# Domino_USB_MicroSD.net
KiCad netlist of a schematic drawn in EAGLE
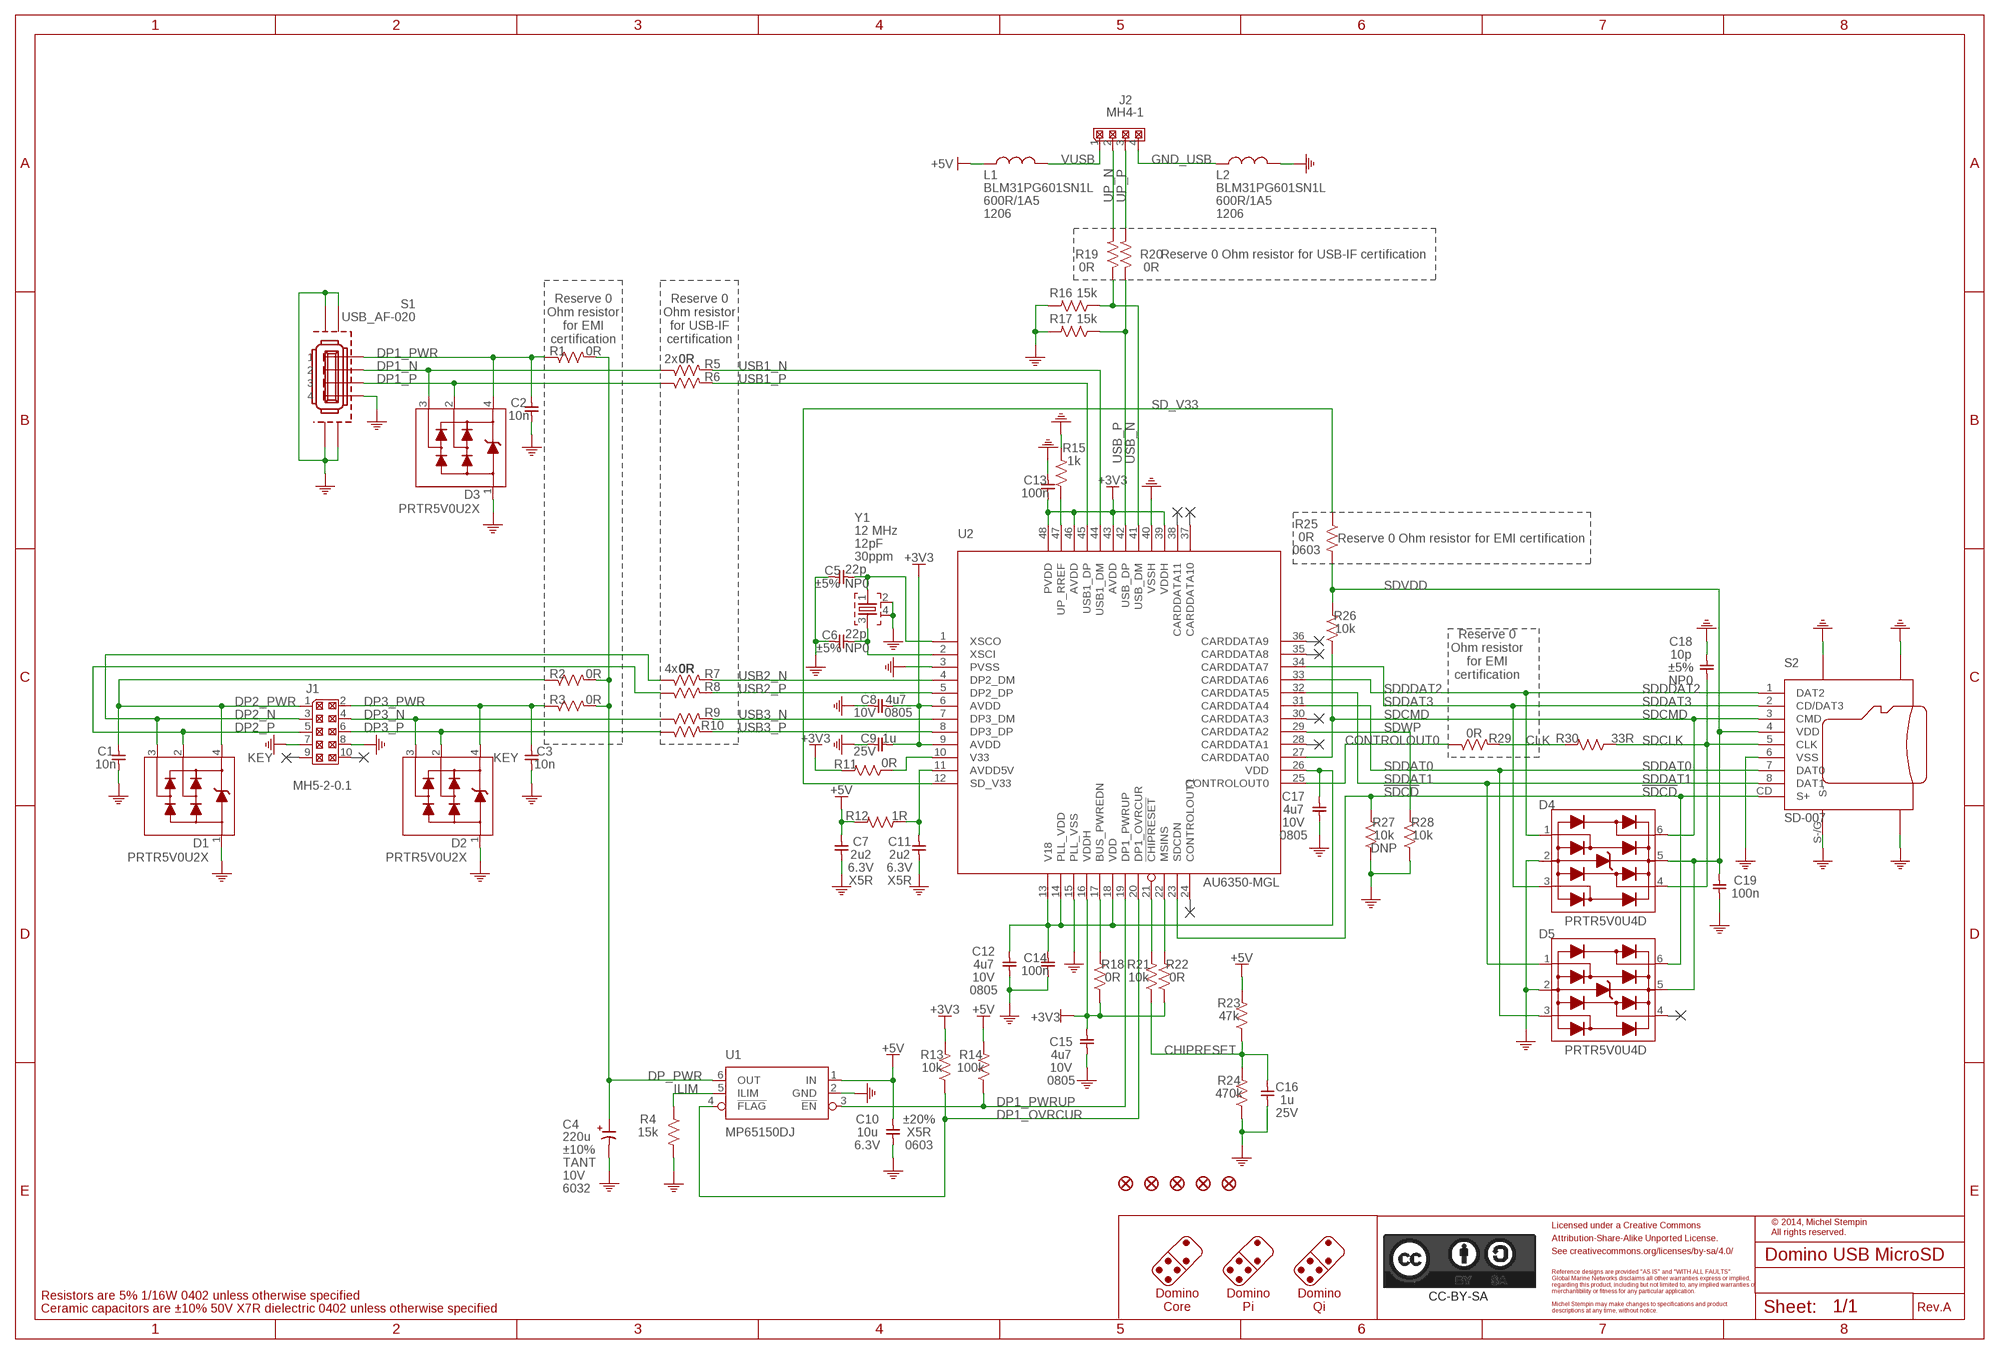
[diagram p0: schematic, sheet 1]

(export (version "E")
  (design (tool "Eeschema 10.0.6"))
  (components
    (comp (ref "C1")
      (value "10n")
      (footprint "eagle-import:C0402")
      (fields (field (name "PARTNO") "C0402_10n_X7R_10%_CER_50V"))
      (libsource (lib "eagle-import") (part "CAP_0402"))
    )
    (comp (ref "C2")
      (value "10n")
      (footprint "eagle-import:C0402")
      (fields (field (name "PARTNO") "C0402_10n_X7R_10%_CER_50V"))
      (libsource (lib "eagle-import") (part "CAP_0402"))
    )
    (comp (ref "C3")
      (value "10n")
      (footprint "eagle-import:C0402")
      (fields (field (name "PARTNO") "C0402_10n_X7R_10%_CER_50V"))
      (libsource (lib "eagle-import") (part "CAP_0402"))
    )
    (comp (ref "C4")
      (value "220u")
      (footprint "eagle-import:C_6032-25")
      (fields
        (field (name "SIZE") "6032")
        (field (name "TYPE") "TANT")
        (field (name "PARTNO") "CPOLC-6032_220u_20%_TANT_10V")
        (field (name "TOL") "±10%")
        (field (name "VOLT") "10V")
      )
      (libsource (lib "eagle-import") (part "CPOL_?C/6032-25"))
    )
    (comp (ref "C5")
      (value "22p")
      (footprint "eagle-import:C0402")
      (fields
        (field (name "PARTNO") "C0402_22p_NP0_5%_CER_50V")
        (field (name "TC") "NP0")
        (field (name "TOL") "±5%")
      )
      (libsource (lib "eagle-import") (part "CAP_0402"))
    )
    (comp (ref "C6")
      (value "22p")
      (footprint "eagle-import:C0402")
      (fields
        (field (name "PARTNO") "C0402_22p_NP0_5%_CER_50V")
        (field (name "TC") "NP0")
        (field (name "TOL") "±5%")
      )
      (libsource (lib "eagle-import") (part "CAP_0402"))
    )
    (comp (ref "C7")
      (value "2u2")
      (footprint "eagle-import:C0402")
      (fields
        (field (name "PARTNO") "C0402_2u2_X5R_10%_CER_6V3")
        (field (name "TC") "X5R")
        (field (name "VOLT") "6.3V")
      )
      (libsource (lib "eagle-import") (part "CAP_0402"))
    )
    (comp (ref "C8")
      (value "4u7")
      (footprint "eagle-import:C0805")
      (fields
        (field (name "SIZE") "0805")
        (field (name "PARTNO") "C0805_4u7_X7R_10%_CER_6V3")
        (field (name "VOLT") "10V")
      )
      (libsource (lib "eagle-import") (part "CAP_0805"))
    )
    (comp (ref "C9")
      (value "1u")
      (footprint "eagle-import:C0402")
      (fields (field (name "PARTNO") "C0402_1u_X7R_10%_CER_25V") (field (name "VOLT") "25V"))
      (libsource (lib "eagle-import") (part "CAP_0402"))
    )
    (comp (ref "C10")
      (value "10u")
      (footprint "eagle-import:C0603")
      (fields
        (field (name "SIZE") "0603")
        (field (name "PARTNO") "C0603_10u_X5R_20%_CER_6V3")
        (field (name "TC") "X5R")
        (field (name "TOL") "±20%")
        (field (name "VOLT") "6.3V")
      )
      (libsource (lib "eagle-import") (part "CAP_0603"))
    )
    (comp (ref "C11")
      (value "2u2")
      (footprint "eagle-import:C0402")
      (fields
        (field (name "PARTNO") "C0402_2u2_X5R_10%_CER_6V3")
        (field (name "TC") "X5R")
        (field (name "VOLT") "6.3V")
      )
      (libsource (lib "eagle-import") (part "CAP_0402"))
    )
    (comp (ref "C12")
      (value "4u7")
      (footprint "eagle-import:C0805")
      (fields
        (field (name "SIZE") "0805")
        (field (name "PARTNO") "C0805_4u7_X7R_10%_CER_6V3")
        (field (name "VOLT") "10V")
      )
      (libsource (lib "eagle-import") (part "CAP_0805"))
    )
    (comp (ref "C13")
      (value "100n")
      (footprint "eagle-import:C0402")
      (fields (field (name "PARTNO") "C0402_100n_X7R_10%_CER_50V"))
      (libsource (lib "eagle-import") (part "CAP_0402"))
    )
    (comp (ref "C14")
      (value "100n")
      (footprint "eagle-import:C0402")
      (fields (field (name "PARTNO") "C0402_100n_X7R_10%_CER_50V"))
      (libsource (lib "eagle-import") (part "CAP_0402"))
    )
    (comp (ref "C15")
      (value "4u7")
      (footprint "eagle-import:C0805")
      (fields
        (field (name "SIZE") "0805")
        (field (name "PARTNO") "C0805_4u7_X7R_10%_CER_6V3")
        (field (name "VOLT") "10V")
      )
      (libsource (lib "eagle-import") (part "CAP_0805"))
    )
    (comp (ref "C16")
      (value "1u")
      (footprint "eagle-import:C0402")
      (fields (field (name "PARTNO") "C0402_1u_X7R_10%_CER_25V") (field (name "VOLT") "25V"))
      (libsource (lib "eagle-import") (part "CAP_0402"))
    )
    (comp (ref "C17")
      (value "4u7")
      (footprint "eagle-import:C0805")
      (fields
        (field (name "SIZE") "0805")
        (field (name "PARTNO") "C0805_4u7_X7R_10%_CER_6V3")
        (field (name "VOLT") "10V")
      )
      (libsource (lib "eagle-import") (part "CAP_0805"))
    )
    (comp (ref "C18")
      (value "10p")
      (footprint "eagle-import:C0402")
      (fields
        (field (name "PARTNO") "C0402_10p_NP0_5%_CER_50V")
        (field (name "TC") "NP0")
        (field (name "TOL") "±5%")
      )
      (libsource (lib "eagle-import") (part "CAP_0402"))
    )
    (comp (ref "C19")
      (value "100n")
      (footprint "eagle-import:C0402")
      (fields (field (name "PARTNO") "C0402_100n_X7R_10%_CER_50V"))
      (libsource (lib "eagle-import") (part "CAP_0402"))
    )
    (comp (ref "CC-BY-SA1")
      (value "CC-BY-SA_LOGO")
      (footprint "eagle-import:CC-BY-SA_LOGO")
      (libsource (lib "eagle-import") (part "CC-BY-SA_LOGO"))
    )
    (comp (ref "D1")
      (value "PRTR5V0U2X")
      (footprint "eagle-import:SOT143B")
      (libsource (lib "eagle-import") (part "PRTR5V0U2X"))
    )
    (comp (ref "D2")
      (value "PRTR5V0U2X")
      (footprint "eagle-import:SOT143B")
      (libsource (lib "eagle-import") (part "PRTR5V0U2X"))
    )
    (comp (ref "D3")
      (value "PRTR5V0U2X")
      (footprint "eagle-import:SOT143B")
      (libsource (lib "eagle-import") (part "PRTR5V0U2X"))
    )
    (comp (ref "D4")
      (value "PRTR5V0U4D")
      (footprint "eagle-import:SOT23-6")
      (libsource (lib "eagle-import") (part "PRTR5V0U4D"))
    )
    (comp (ref "D5")
      (value "PRTR5V0U4D")
      (footprint "eagle-import:SOT23-6")
      (libsource (lib "eagle-import") (part "PRTR5V0U4D"))
    )
    (comp (ref "F1")
      (value "FIDUCIAL")
      (footprint "eagle-import:FIDUCIAL")
      (libsource (lib "eagle-import") (part "FIDUCIAL"))
    )
    (comp (ref "F2")
      (value "FIDUCIAL")
      (footprint "eagle-import:FIDUCIAL")
      (libsource (lib "eagle-import") (part "FIDUCIAL"))
    )
    (comp (ref "F4")
      (value "FIDUCIAL")
      (footprint "eagle-import:FIDUCIAL")
      (libsource (lib "eagle-import") (part "FIDUCIAL"))
    )
    (comp (ref "F5")
      (value "FIDUCIAL")
      (footprint "eagle-import:FIDUCIAL")
      (libsource (lib "eagle-import") (part "FIDUCIAL"))
    )
    (comp (ref "F6")
      (value "FIDUCIAL")
      (footprint "eagle-import:FIDUCIAL")
      (libsource (lib "eagle-import") (part "FIDUCIAL"))
    )
    (comp (ref "J1")
      (value "MH5-2-0.1")
      (footprint "eagle-import:MH05-2-0.1")
      (libsource (lib "eagle-import") (part "MH5-2"))
    )
    (comp (ref "J2")
      (value "MH4-1")
      (footprint "eagle-import:MH4-1-0.1")
      (fields (field (name "PARTNO") "MH4-1-0.1"))
      (libsource (lib "eagle-import") (part "MH4-1"))
    )
    (comp (ref "L1")
      (value "BLM31PG601SN1L")
      (footprint "eagle-import:FB1206")
      (fields (field (name "SIZE") "1206") (field (name "OPT") "600R/1A5"))
      (libsource (lib "eagle-import") (part "FB_1206"))
    )
    (comp (ref "L2")
      (value "BLM31PG601SN1L")
      (footprint "eagle-import:FB1206")
      (fields (field (name "SIZE") "1206") (field (name "OPT") "600R/1A5"))
      (libsource (lib "eagle-import") (part "FB_1206"))
    )
    (comp (ref "R1")
      (value "0R")
      (footprint "eagle-import:R0402")
      (fields (field (name "PARTNO") "R0402_0R_5%_62.5mW"))
      (libsource (lib "eagle-import") (part "RES_0402"))
    )
    (comp (ref "R2")
      (value "0R")
      (footprint "eagle-import:R0402")
      (fields (field (name "PARTNO") "R0402_0R_5%_62.5mW"))
      (libsource (lib "eagle-import") (part "RES_0402"))
    )
    (comp (ref "R3")
      (value "0R")
      (footprint "eagle-import:R0402")
      (fields (field (name "PARTNO") "R0402_0R_5%_62.5mW"))
      (libsource (lib "eagle-import") (part "RES_0402"))
    )
    (comp (ref "R4")
      (value "15k")
      (footprint "eagle-import:R0402")
      (fields (field (name "PARTNO") "R0402_15k_5%_62.5mW"))
      (libsource (lib "eagle-import") (part "RES_0402"))
    )
    (comp (ref "R5")
      (value "0R")
      (footprint "eagle-import:R0402")
      (fields (field (name "PARTNO") "R0402_0R_5%_62.5mW"))
      (libsource (lib "eagle-import") (part "RES_0402"))
    )
    (comp (ref "R6")
      (value "0R")
      (footprint "eagle-import:R0402")
      (fields (field (name "PARTNO") "R0402_0R_5%_62.5mW"))
      (libsource (lib "eagle-import") (part "RES_0402"))
    )
    (comp (ref "R7")
      (value "0R")
      (footprint "eagle-import:R0402")
      (fields (field (name "PARTNO") "R0402_0R_5%_62.5mW"))
      (libsource (lib "eagle-import") (part "RES_0402"))
    )
    (comp (ref "R8")
      (value "0R")
      (footprint "eagle-import:R0402")
      (fields (field (name "PARTNO") "R0402_0R_5%_62.5mW"))
      (libsource (lib "eagle-import") (part "RES_0402"))
    )
    (comp (ref "R9")
      (value "0R")
      (footprint "eagle-import:R0402")
      (fields (field (name "PARTNO") "R0402_0R_5%_62.5mW"))
      (libsource (lib "eagle-import") (part "RES_0402"))
    )
    (comp (ref "R10")
      (value "0R")
      (footprint "eagle-import:R0402")
      (fields (field (name "PARTNO") "R0402_0R_5%_62.5mW"))
      (libsource (lib "eagle-import") (part "RES_0402"))
    )
    (comp (ref "R11")
      (value "0R")
      (footprint "eagle-import:R0402")
      (fields (field (name "PARTNO") "R0402_0R_5%_62.5mW"))
      (libsource (lib "eagle-import") (part "RES_0402"))
    )
    (comp (ref "R12")
      (value "1R")
      (footprint "eagle-import:R0402")
      (fields (field (name "PARTNO") "R0402_1R_5%_62.5mW"))
      (libsource (lib "eagle-import") (part "RES_0402"))
    )
    (comp (ref "R13")
      (value "10k")
      (footprint "eagle-import:R0402")
      (fields (field (name "PARTNO") "R0402_10k_5%_62.5mW"))
      (libsource (lib "eagle-import") (part "RES_0402"))
    )
    (comp (ref "R14")
      (value "100k")
      (footprint "eagle-import:R0402")
      (fields (field (name "PARTNO") "R0402_100k_5%_62.5mW"))
      (libsource (lib "eagle-import") (part "RES_0402"))
    )
    (comp (ref "R15")
      (value "1k")
      (footprint "eagle-import:R0402")
      (fields (field (name "PARTNO") "R0402_1k_5%_62.5mW"))
      (libsource (lib "eagle-import") (part "RES_0402"))
    )
    (comp (ref "R16")
      (value "15k")
      (footprint "eagle-import:R0402")
      (fields (field (name "PARTNO") "R0402_15k_5%_62.5mW"))
      (libsource (lib "eagle-import") (part "RES_0402"))
    )
    (comp (ref "R17")
      (value "15k")
      (footprint "eagle-import:R0402")
      (fields (field (name "PARTNO") "R0402_15k_5%_62.5mW"))
      (libsource (lib "eagle-import") (part "RES_0402"))
    )
    (comp (ref "R18")
      (value "0R")
      (footprint "eagle-import:R0402")
      (fields (field (name "PARTNO") "R0402_0R_5%_62.5mW"))
      (libsource (lib "eagle-import") (part "RES_0402"))
    )
    (comp (ref "R19")
      (value "0R")
      (footprint "eagle-import:R0402")
      (fields (field (name "PARTNO") "R0402_0R_5%_62.5mW"))
      (libsource (lib "eagle-import") (part "RES_0402"))
    )
    (comp (ref "R20")
      (value "0R")
      (footprint "eagle-import:R0402")
      (fields (field (name "PARTNO") "R0402_0R_5%_62.5mW"))
      (libsource (lib "eagle-import") (part "RES_0402"))
    )
    (comp (ref "R21")
      (value "10k")
      (footprint "eagle-import:R0402")
      (fields (field (name "PARTNO") "R0402_10k_5%_62.5mW"))
      (libsource (lib "eagle-import") (part "RES_0402"))
    )
    (comp (ref "R22")
      (value "0R")
      (footprint "eagle-import:R0402")
      (fields (field (name "PARTNO") "R0402_0R_5%_62.5mW"))
      (libsource (lib "eagle-import") (part "RES_0402"))
    )
    (comp (ref "R23")
      (value "47k")
      (footprint "eagle-import:R0402")
      (fields (field (name "PARTNO") "R0402_47k_5%_62.5mW"))
      (libsource (lib "eagle-import") (part "RES_0402"))
    )
    (comp (ref "R24")
      (value "470k")
      (footprint "eagle-import:R0402")
      (fields (field (name "PARTNO") "R0402_470k_5%_62.5mW"))
      (libsource (lib "eagle-import") (part "RES_0402"))
    )
    (comp (ref "R25")
      (value "0R")
      (footprint "eagle-import:R0603")
      (fields (field (name "SIZE") "0603") (field (name "PARTNO") "R0603_0R_5%_125mW"))
      (libsource (lib "eagle-import") (part "RES_0603"))
    )
    (comp (ref "R26")
      (value "10k")
      (footprint "eagle-import:R0402")
      (fields (field (name "PARTNO") "R0402_10k_5%_62.5mW"))
      (libsource (lib "eagle-import") (part "RES_0402"))
    )
    (comp (ref "R27")
      (value "10k")
      (footprint "eagle-import:R0402")
      (fields (field (name "PARTNO") "R0402_10k_5%_62.5mW"))
      (libsource (lib "eagle-import") (part "RES_0402"))
    )
    (comp (ref "R28")
      (value "10k")
      (footprint "eagle-import:R0402")
      (fields (field (name "PARTNO") "R0402_10k_5%_62.5mW"))
      (libsource (lib "eagle-import") (part "RES_0402"))
    )
    (comp (ref "R29")
      (value "0R")
      (footprint "eagle-import:R0402")
      (fields (field (name "PARTNO") "R0402_0R_5%_62.5mW"))
      (libsource (lib "eagle-import") (part "RES_0402"))
    )
    (comp (ref "R30")
      (value "33R")
      (footprint "eagle-import:R0402")
      (fields (field (name "PARTNO") "R0402_33R_5%_62.5mW"))
      (libsource (lib "eagle-import") (part "RES_0402"))
    )
    (comp (ref "S1")
      (value "USB_AF-020")
      (footprint "eagle-import:USB_AF-020")
      (libsource (lib "eagle-import") (part "USB_AF-020"))
    )
    (comp (ref "S2")
      (value "SD-007")
      (footprint "eagle-import:SD-007")
      (libsource (lib "eagle-import") (part "MICRO-SD"))
    )
    (comp (ref "U1")
      (value "MP65150DJ")
      (footprint "eagle-import:SOT23-6")
      (libsource (lib "eagle-import") (part "MP65150DJ"))
    )
    (comp (ref "U2")
      (value "AU6350-MGL")
      (footprint "eagle-import:LQFP-48_7X7")
      (libsource (lib "eagle-import") (part "AU6350-MGL"))
    )
    (comp (ref "Y1")
      (value "12 MHz")
      (footprint "eagle-import:CRYSTAL_32X25")
      (fields
        (field (name "LOAD") "12pF")
        (field (name "PARTNO") "CRYSTAL_32X25_2SH_12PF_30PPM")
        (field (name "TOL") "30ppm")
      )
      (libsource (lib "eagle-import") (part "CRYSTAL_2SH"))
    )
  )
  (nets
    (net (code "1") (name "+3V3") (class "Default")
      (node (ref "C13") (pin "2") (pinfunction "2_2") (pintype "passive"))
      (node (ref "C15") (pin "2") (pinfunction "2_2") (pintype "passive"))
      (node (ref "C8") (pin "2") (pinfunction "2_2") (pintype "passive"))
      (node (ref "C9") (pin "2") (pinfunction "2_2") (pintype "passive"))
      (node (ref "R11") (pin "2") (pinfunction "2_2") (pintype "passive"))
      (node (ref "R13") (pin "2") (pinfunction "2_2") (pintype "passive"))
      (node (ref "R18") (pin "1") (pinfunction "1_1") (pintype "passive"))
      (node (ref "R22") (pin "1") (pinfunction "1_1") (pintype "passive"))
      (node (ref "U2") (pin "16") (pinfunction "VDDH_16") (pintype "power_in"))
      (node (ref "U2") (pin "39") (pinfunction "VDDH_39") (pintype "power_in"))
      (node (ref "U2") (pin "43") (pinfunction "AVDD_43") (pintype "power_in"))
      (node (ref "U2") (pin "46") (pinfunction "AVDD_46") (pintype "power_in"))
      (node (ref "U2") (pin "48") (pinfunction "PVDD_48") (pintype "power_in"))
      (node (ref "U2") (pin "6") (pinfunction "AVDD_6") (pintype "power_in"))
      (node (ref "U2") (pin "9") (pinfunction "AVDD_9") (pintype "power_in"))
    )
    (net (code "2") (name "+5V") (class "Default")
      (node (ref "C10") (pin "1") (pinfunction "1_1") (pintype "passive"))
      (node (ref "C7") (pin "1") (pinfunction "1_1") (pintype "passive"))
      (node (ref "L1") (pin "2") (pinfunction "2_2") (pintype "passive"))
      (node (ref "R12") (pin "2") (pinfunction "2_2") (pintype "passive"))
      (node (ref "R14") (pin "2") (pinfunction "2_2") (pintype "passive"))
      (node (ref "R23") (pin "2") (pinfunction "2_2") (pintype "passive"))
      (node (ref "U1") (pin "1") (pinfunction "IN_1") (pintype "power_in"))
    )
    (net (code "3") (name "/CHIPRESET") (class "Default")
      (node (ref "C16") (pin "1") (pinfunction "1_1") (pintype "passive"))
      (node (ref "R21") (pin "1") (pinfunction "1_1") (pintype "passive"))
      (node (ref "R23") (pin "1") (pinfunction "1_1") (pintype "passive"))
      (node (ref "R24") (pin "2") (pinfunction "2_2") (pintype "passive"))
    )
    (net (code "4") (name "/CLK") (class "Default")
      (node (ref "R29") (pin "2") (pinfunction "2_2") (pintype "passive"))
      (node (ref "R30") (pin "2") (pinfunction "2_2") (pintype "passive"))
    )
    (net (code "5") (name "/CONTROLOUT0") (class "Default")
      (node (ref "R29") (pin "1") (pinfunction "1_1") (pintype "passive"))
      (node (ref "U2") (pin "25") (pinfunction "CONTROLOUT0_25") (pintype "output"))
    )
    (net (code "6") (name "/DP1_N") (class "Default")
      (node (ref "D3") (pin "3") (pinfunction "P$3_3") (pintype "passive"))
      (node (ref "R5") (pin "1") (pinfunction "1_1") (pintype "passive"))
      (node (ref "S1") (pin "2") (pinfunction "2_2") (pintype "passive"))
    )
    (net (code "7") (name "/DP1_OVRCUR") (class "Default")
      (node (ref "R13") (pin "1") (pinfunction "1_1") (pintype "passive"))
      (node (ref "U1") (pin "4") (pinfunction "~{FLAG}_4") (pintype "open_collector"))
      (node (ref "U2") (pin "20") (pinfunction "DP1_OVRCUR_20") (pintype "input"))
    )
    (net (code "8") (name "/DP1_P") (class "Default")
      (node (ref "D3") (pin "2") (pinfunction "P$2_2") (pintype "passive"))
      (node (ref "R6") (pin "1") (pinfunction "1_1") (pintype "passive"))
      (node (ref "S1") (pin "3") (pinfunction "3_3") (pintype "passive"))
    )
    (net (code "9") (name "/DP1_PWR") (class "Default")
      (node (ref "C2") (pin "1") (pinfunction "1_1") (pintype "passive"))
      (node (ref "D3") (pin "4") (pinfunction "P$4_4") (pintype "passive"))
      (node (ref "R1") (pin "1") (pinfunction "1_1") (pintype "passive"))
      (node (ref "S1") (pin "1") (pinfunction "1_1") (pintype "passive"))
    )
    (net (code "10") (name "/DP1_PWRUP") (class "Default")
      (node (ref "R14") (pin "1") (pinfunction "1_1") (pintype "passive"))
      (node (ref "U1") (pin "3") (pinfunction "~{EN}_3") (pintype "input"))
      (node (ref "U2") (pin "19") (pinfunction "DP1_PWRUP_19") (pintype "output"))
    )
    (net (code "11") (name "/DP2_N") (class "Default")
      (node (ref "D1") (pin "3") (pinfunction "P$3_3") (pintype "passive"))
      (node (ref "J1") (pin "3") (pinfunction "3_3") (pintype "passive"))
      (node (ref "R7") (pin "1") (pinfunction "1_1") (pintype "passive"))
    )
    (net (code "12") (name "/DP2_P") (class "Default")
      (node (ref "D1") (pin "2") (pinfunction "P$2_2") (pintype "passive"))
      (node (ref "J1") (pin "5") (pinfunction "5_5") (pintype "passive"))
      (node (ref "R8") (pin "1") (pinfunction "1_1") (pintype "passive"))
    )
    (net (code "13") (name "/DP2_PWR") (class "Default")
      (node (ref "C1") (pin "1") (pinfunction "1_1") (pintype "passive"))
      (node (ref "D1") (pin "4") (pinfunction "P$4_4") (pintype "passive"))
      (node (ref "J1") (pin "1") (pinfunction "1_1") (pintype "passive"))
      (node (ref "R2") (pin "1") (pinfunction "1_1") (pintype "passive"))
    )
    (net (code "14") (name "/DP3_N") (class "Default")
      (node (ref "D2") (pin "3") (pinfunction "P$3_3") (pintype "passive"))
      (node (ref "J1") (pin "4") (pinfunction "4_4") (pintype "passive"))
      (node (ref "R9") (pin "1") (pinfunction "1_1") (pintype "passive"))
    )
    (net (code "15") (name "/DP3_P") (class "Default")
      (node (ref "D2") (pin "2") (pinfunction "P$2_2") (pintype "passive"))
      (node (ref "J1") (pin "6") (pinfunction "6_6") (pintype "passive"))
      (node (ref "R10") (pin "1") (pinfunction "1_1") (pintype "passive"))
    )
    (net (code "16") (name "/DP3_PWR") (class "Default")
      (node (ref "C3") (pin "1") (pinfunction "1_1") (pintype "passive"))
      (node (ref "D2") (pin "4") (pinfunction "P$4_4") (pintype "passive"))
      (node (ref "J1") (pin "2") (pinfunction "2_2") (pintype "passive"))
      (node (ref "R3") (pin "1") (pinfunction "1_1") (pintype "passive"))
    )
    (net (code "17") (name "/DP_PWR") (class "Default")
      (node (ref "C4") (pin "1") (pinfunction "+_1") (pintype "passive"))
      (node (ref "R1") (pin "2") (pinfunction "2_2") (pintype "passive"))
      (node (ref "R2") (pin "2") (pinfunction "2_2") (pintype "passive"))
      (node (ref "R3") (pin "2") (pinfunction "2_2") (pintype "passive"))
      (node (ref "U1") (pin "6") (pinfunction "OUT_6") (pintype "power_in"))
    )
    (net (code "18") (name "/GND_USB") (class "Default")
      (node (ref "J2") (pin "4") (pinfunction "4_4") (pintype "passive"))
      (node (ref "L2") (pin "2") (pinfunction "2_2") (pintype "passive"))
    )
    (net (code "19") (name "/ILIM") (class "Default")
      (node (ref "R4") (pin "1") (pinfunction "1_1") (pintype "passive"))
      (node (ref "U1") (pin "5") (pinfunction "ILIM_5") (pintype "passive"))
    )
    (net (code "20") (name "/SDCLK") (class "Default")
      (node (ref "C18") (pin "1") (pinfunction "1_1") (pintype "passive"))
      (node (ref "D4") (pin "4") (pinfunction "I/O3_4") (pintype "passive"))
      (node (ref "R30") (pin "1") (pinfunction "1_1") (pintype "passive"))
      (node (ref "S2") (pin "5") (pinfunction "CLK_5") (pintype "input"))
    )
    (net (code "21") (name "/SDCMD") (class "Default")
      (node (ref "D4") (pin "6") (pinfunction "I/O4_6") (pintype "passive"))
      (node (ref "R26") (pin "1") (pinfunction "1_1") (pintype "passive"))
      (node (ref "S2") (pin "3") (pinfunction "CMD_3") (pintype "input"))
      (node (ref "U2") (pin "27") (pinfunction "CARDDATA0_27") (pintype "bidirectional"))
    )
    (net (code "22") (name "/SDDAT0") (class "Default")
      (node (ref "D5") (pin "3") (pinfunction "I/O2_3") (pintype "passive"))
      (node (ref "S2") (pin "7") (pinfunction "DAT0_7") (pintype "bidirectional"))
      (node (ref "U2") (pin "31") (pinfunction "CARDDATA4_31") (pintype "bidirectional"))
    )
    (net (code "23") (name "/SDDAT1") (class "Default")
      (node (ref "D5") (pin "1") (pinfunction "I/O1_1") (pintype "passive"))
      (node (ref "S2") (pin "8") (pinfunction "DAT1_8") (pintype "bidirectional"))
      (node (ref "U2") (pin "32") (pinfunction "CARDDATA5_32") (pintype "bidirectional"))
    )
    (net (code "24") (name "/SDDAT3") (class "Default")
      (node (ref "D4") (pin "3") (pinfunction "I/O2_3") (pintype "passive"))
      (node (ref "S2") (pin "2") (pinfunction "CD/DAT3_2") (pintype "bidirectional"))
      (node (ref "U2") (pin "34") (pinfunction "CARDDATA7_34") (pintype "bidirectional"))
    )
    (net (code "25") (name "/SDDDAT2") (class "Default")
      (node (ref "D4") (pin "1") (pinfunction "I/O1_1") (pintype "passive"))
      (node (ref "S2") (pin "1") (pinfunction "DAT2_1") (pintype "bidirectional"))
      (node (ref "U2") (pin "33") (pinfunction "CARDDATA6_33") (pintype "bidirectional"))
    )
    (net (code "26") (name "/SDVDD") (class "Default")
      (node (ref "C19") (pin "1") (pinfunction "1_1") (pintype "passive"))
      (node (ref "D4") (pin "5") (pinfunction "VCC_5") (pintype "passive"))
      (node (ref "D5") (pin "5") (pinfunction "VCC_5") (pintype "passive"))
      (node (ref "R25") (pin "2") (pinfunction "2_2") (pintype "passive"))
      (node (ref "R26") (pin "2") (pinfunction "2_2") (pintype "passive"))
      (node (ref "S2") (pin "4") (pinfunction "VDD_4") (pintype "power_in"))
    )
    (net (code "27") (name "/SDWP") (class "Default")
      (node (ref "R28") (pin "2") (pinfunction "2_2") (pintype "passive"))
      (node (ref "U2") (pin "29") (pinfunction "CARDDATA2_29") (pintype "bidirectional"))
    )
    (net (code "28") (name "/SD_V33") (class "Default")
      (node (ref "R25") (pin "1") (pinfunction "1_1") (pintype "passive"))
      (node (ref "U2") (pin "12") (pinfunction "SD_V33_12") (pintype "power_in"))
    )
    (net (code "29") (name "/UP_N") (class "Default")
      (node (ref "J2") (pin "2") (pinfunction "2_2") (pintype "passive"))
      (node (ref "R19") (pin "2") (pinfunction "2_2") (pintype "passive"))
    )
    (net (code "30") (name "/UP_P") (class "Default")
      (node (ref "J2") (pin "3") (pinfunction "3_3") (pintype "passive"))
      (node (ref "R20") (pin "2") (pinfunction "2_2") (pintype "passive"))
    )
    (net (code "31") (name "/USB1_N") (class "Default")
      (node (ref "R5") (pin "2") (pinfunction "2_2") (pintype "passive"))
      (node (ref "U2") (pin "44") (pinfunction "USB1_DM_44") (pintype "passive"))
    )
    (net (code "32") (name "/USB1_P") (class "Default")
      (node (ref "R6") (pin "2") (pinfunction "2_2") (pintype "passive"))
      (node (ref "U2") (pin "45") (pinfunction "USB1_DP_45") (pintype "passive"))
    )
    (net (code "33") (name "/USB2_N") (class "Default")
      (node (ref "R7") (pin "2") (pinfunction "2_2") (pintype "passive"))
      (node (ref "U2") (pin "4") (pinfunction "DP2_DM_4") (pintype "passive"))
    )
    (net (code "34") (name "/USB2_P") (class "Default")
      (node (ref "R8") (pin "2") (pinfunction "2_2") (pintype "passive"))
      (node (ref "U2") (pin "5") (pinfunction "DP2_DP_5") (pintype "passive"))
    )
    (net (code "35") (name "/USB3_N") (class "Default")
      (node (ref "R9") (pin "2") (pinfunction "2_2") (pintype "passive"))
      (node (ref "U2") (pin "7") (pinfunction "DP3_DM_7") (pintype "passive"))
    )
    (net (code "36") (name "/USB3_P") (class "Default")
      (node (ref "R10") (pin "2") (pinfunction "2_2") (pintype "passive"))
      (node (ref "U2") (pin "8") (pinfunction "DP3_DP_8") (pintype "passive"))
    )
    (net (code "37") (name "/USB_N") (class "Default")
      (node (ref "R16") (pin "1") (pinfunction "1_1") (pintype "passive"))
      (node (ref "R19") (pin "1") (pinfunction "1_1") (pintype "passive"))
      (node (ref "U2") (pin "41") (pinfunction "USB_DM_41") (pintype "passive"))
    )
    (net (code "38") (name "/USB_P") (class "Default")
      (node (ref "R17") (pin "1") (pinfunction "1_1") (pintype "passive"))
      (node (ref "R20") (pin "1") (pinfunction "1_1") (pintype "passive"))
      (node (ref "U2") (pin "42") (pinfunction "USB_DP_42") (pintype "passive"))
    )
    (net (code "39") (name "/VUSB") (class "Default")
      (node (ref "J2") (pin "1") (pinfunction "1_1") (pintype "passive"))
      (node (ref "L1") (pin "1") (pinfunction "1_1") (pintype "passive"))
    )
    (net (code "40") (name "/~{SDCD}") (class "Default")
      (node (ref "D5") (pin "6") (pinfunction "I/O4_6") (pintype "passive"))
      (node (ref "R27") (pin "2") (pinfunction "2_2") (pintype "passive"))
      (node (ref "S2") (pin "CD") (pinfunction "S+_CD") (pintype "output"))
      (node (ref "U2") (pin "23") (pinfunction "SDCDN_23") (pintype "input"))
    )
    (net (code "41") (name "GND") (class "Default")
      (node (ref "C1") (pin "2") (pinfunction "2_2") (pintype "passive"))
      (node (ref "C10") (pin "2") (pinfunction "2_2") (pintype "passive"))
      (node (ref "C11") (pin "2") (pinfunction "2_2") (pintype "passive"))
      (node (ref "C12") (pin "1") (pinfunction "1_1") (pintype "passive"))
      (node (ref "C13") (pin "1") (pinfunction "1_1") (pintype "passive"))
      (node (ref "C14") (pin "2") (pinfunction "2_2") (pintype "passive"))
      (node (ref "C15") (pin "1") (pinfunction "1_1") (pintype "passive"))
      (node (ref "C16") (pin "2") (pinfunction "2_2") (pintype "passive"))
      (node (ref "C17") (pin "1") (pinfunction "1_1") (pintype "passive"))
      (node (ref "C18") (pin "2") (pinfunction "2_2") (pintype "passive"))
      (node (ref "C19") (pin "2") (pinfunction "2_2") (pintype "passive"))
      (node (ref "C2") (pin "2") (pinfunction "2_2") (pintype "passive"))
      (node (ref "C3") (pin "2") (pinfunction "2_2") (pintype "passive"))
      (node (ref "C4") (pin "2") (pinfunction "-_2") (pintype "passive"))
      (node (ref "C5") (pin "1") (pinfunction "1_1") (pintype "passive"))
      (node (ref "C6") (pin "1") (pinfunction "1_1") (pintype "passive"))
      (node (ref "C7") (pin "2") (pinfunction "2_2") (pintype "passive"))
      (node (ref "C8") (pin "1") (pinfunction "1_1") (pintype "passive"))
      (node (ref "C9") (pin "1") (pinfunction "1_1") (pintype "passive"))
      (node (ref "D1") (pin "1") (pinfunction "P$1_1") (pintype "passive"))
      (node (ref "D2") (pin "1") (pinfunction "P$1_1") (pintype "passive"))
      (node (ref "D3") (pin "1") (pinfunction "P$1_1") (pintype "passive"))
      (node (ref "D4") (pin "2") (pinfunction "GND_2") (pintype "passive"))
      (node (ref "D5") (pin "2") (pinfunction "GND_2") (pintype "passive"))
      (node (ref "J1") (pin "7") (pinfunction "7_7") (pintype "passive"))
      (node (ref "J1") (pin "8") (pinfunction "8_8") (pintype "passive"))
      (node (ref "L2") (pin "1") (pinfunction "1_1") (pintype "passive"))
      (node (ref "R15") (pin "2") (pinfunction "2_2") (pintype "passive"))
      (node (ref "R16") (pin "2") (pinfunction "2_2") (pintype "passive"))
      (node (ref "R17") (pin "2") (pinfunction "2_2") (pintype "passive"))
      (node (ref "R24") (pin "1") (pinfunction "1_1") (pintype "passive"))
      (node (ref "R27") (pin "1") (pinfunction "1_1") (pintype "passive"))
      (node (ref "R28") (pin "1") (pinfunction "1_1") (pintype "passive"))
      (node (ref "R4") (pin "2") (pinfunction "2_2") (pintype "passive"))
      (node (ref "S1") (pin "4") (pinfunction "4_4") (pintype "passive"))
      (node (ref "S1") (pin "G$1") (pinfunction "G_G$1") (pintype "passive"))
      (node (ref "S1") (pin "G$2") (pinfunction "G_G$2") (pintype "passive"))
      (node (ref "S1") (pin "G$3") (pinfunction "G_G$3") (pintype "passive"))
      (node (ref "S1") (pin "G$4") (pinfunction "G_G$4") (pintype "passive"))
      (node (ref "S2") (pin "6") (pinfunction "VSS_6") (pintype "power_in"))
      (node (ref "S2") (pin "G$1") (pinfunction "G_G$1") (pintype "power_in"))
      (node (ref "S2") (pin "G$2") (pinfunction "G_G$2") (pintype "power_in"))
      (node (ref "S2") (pin "G$3") (pinfunction "G_G$3") (pintype "power_in"))
      (node (ref "S2") (pin "S-/G") (pinfunction "S-_S-/G") (pintype "power_in"))
      (node (ref "U1") (pin "2") (pinfunction "GND_2") (pintype "power_in"))
      (node (ref "U2") (pin "15") (pinfunction "PLL_VSS_15") (pintype "power_in"))
      (node (ref "U2") (pin "3") (pinfunction "PVSS_3") (pintype "power_in"))
      (node (ref "U2") (pin "40") (pinfunction "VSSH_40") (pintype "power_in"))
      (node (ref "Y1") (pin "2") (pinfunction "2_2") (pintype "passive"))
      (node (ref "Y1") (pin "4") (pinfunction "4_4") (pintype "passive"))
    )
    (net (code "42") (name "Net-(U2-AVDD5V)") (class "Default")
      (node (ref "C11") (pin "1") (pinfunction "1_1") (pintype "passive"))
      (node (ref "R12") (pin "1") (pinfunction "1_1") (pintype "passive"))
      (node (ref "U2") (pin "11") (pinfunction "AVDD5V_11") (pintype "power_in"))
    )
    (net (code "43") (name "Net-(U2-BUS_PWREDN)") (class "Default")
      (node (ref "R18") (pin "2") (pinfunction "2_2") (pintype "passive"))
      (node (ref "U2") (pin "17") (pinfunction "BUS_PWREDN_17") (pintype "input"))
    )
    (net (code "44") (name "Net-(U2-MSINS)") (class "Default")
      (node (ref "R22") (pin "2") (pinfunction "2_2") (pintype "passive"))
      (node (ref "U2") (pin "22") (pinfunction "MSINS_22") (pintype "input"))
    )
    (net (code "45") (name "Net-(U2-PLL_VDD)") (class "Default")
      (node (ref "C12") (pin "2") (pinfunction "2_2") (pintype "passive"))
      (node (ref "C14") (pin "1") (pinfunction "1_1") (pintype "passive"))
      (node (ref "C17") (pin "2") (pinfunction "2_2") (pintype "passive"))
      (node (ref "U2") (pin "13") (pinfunction "V18_13") (pintype "power_in"))
      (node (ref "U2") (pin "14") (pinfunction "PLL_VDD_14") (pintype "power_in"))
      (node (ref "U2") (pin "18") (pinfunction "VDD_18") (pintype "power_in"))
      (node (ref "U2") (pin "26") (pinfunction "VDD_26") (pintype "power_in"))
    )
    (net (code "46") (name "Net-(U2-UP_RREF)") (class "Default")
      (node (ref "R15") (pin "1") (pinfunction "1_1") (pintype "passive"))
      (node (ref "U2") (pin "47") (pinfunction "UP_RREF_47") (pintype "passive"))
    )
    (net (code "47") (name "Net-(U2-V33)") (class "Default")
      (node (ref "R11") (pin "1") (pinfunction "1_1") (pintype "passive"))
      (node (ref "U2") (pin "10") (pinfunction "V33_10") (pintype "power_in"))
    )
    (net (code "48") (name "Net-(U2-XSCI)") (class "Default")
      (node (ref "C6") (pin "2") (pinfunction "2_2") (pintype "passive"))
      (node (ref "U2") (pin "2") (pinfunction "XSCI_2") (pintype "passive"))
      (node (ref "Y1") (pin "3") (pinfunction "3_3") (pintype "passive"))
    )
    (net (code "49") (name "Net-(U2-XSCO)") (class "Default")
      (node (ref "C5") (pin "2") (pinfunction "2_2") (pintype "passive"))
      (node (ref "U2") (pin "1") (pinfunction "XSCO_1") (pintype "passive"))
      (node (ref "Y1") (pin "1") (pinfunction "1_1") (pintype "passive"))
    )
    (net (code "50") (name "Net-(U2-~{CHIPRESET})") (class "Default")
      (node (ref "R21") (pin "2") (pinfunction "2_2") (pintype "passive"))
      (node (ref "U2") (pin "21") (pinfunction "~{CHIPRESET}_21") (pintype "input"))
    )
    (net (code "51") (name "unconnected-(D5-I{slash}O3-Pad4)") (class "Default")
      (node (ref "D5") (pin "4") (pinfunction "I/O3_4") (pintype "passive"))
    )
    (net (code "52") (name "unconnected-(J1-Pad9)") (class "Default")
      (node (ref "J1") (pin "9") (pinfunction "9_9") (pintype "passive"))
    )
    (net (code "53") (name "unconnected-(J1-Pad10)") (class "Default")
      (node (ref "J1") (pin "10") (pinfunction "10_10") (pintype "passive"))
    )
    (net (code "54") (name "unconnected-(U2-CARDDATA1-Pad28)") (class "Default")
      (node (ref "U2") (pin "28") (pinfunction "CARDDATA1_28") (pintype "bidirectional"))
    )
    (net (code "55") (name "unconnected-(U2-CARDDATA3-Pad30)") (class "Default")
      (node (ref "U2") (pin "30") (pinfunction "CARDDATA3_30") (pintype "bidirectional"))
    )
    (net (code "56") (name "unconnected-(U2-CARDDATA8-Pad35)") (class "Default")
      (node (ref "U2") (pin "35") (pinfunction "CARDDATA8_35") (pintype "bidirectional"))
    )
    (net (code "57") (name "unconnected-(U2-CARDDATA9-Pad36)") (class "Default")
      (node (ref "U2") (pin "36") (pinfunction "CARDDATA9_36") (pintype "bidirectional"))
    )
    (net (code "58") (name "unconnected-(U2-CARDDATA10-Pad37)") (class "Default")
      (node (ref "U2") (pin "37") (pinfunction "CARDDATA10_37") (pintype "bidirectional"))
    )
    (net (code "59") (name "unconnected-(U2-CARDDATA11-Pad38)") (class "Default")
      (node (ref "U2") (pin "38") (pinfunction "CARDDATA11_38") (pintype "bidirectional"))
    )
    (net (code "60") (name "unconnected-(U2-CONTROLOUT1-Pad24)") (class "Default")
      (node (ref "U2") (pin "24") (pinfunction "CONTROLOUT1_24") (pintype "output"))
    )
  )
)
